# SimpleKeyboard.net
KiCad netlist of a schematic drawn in EAGLE
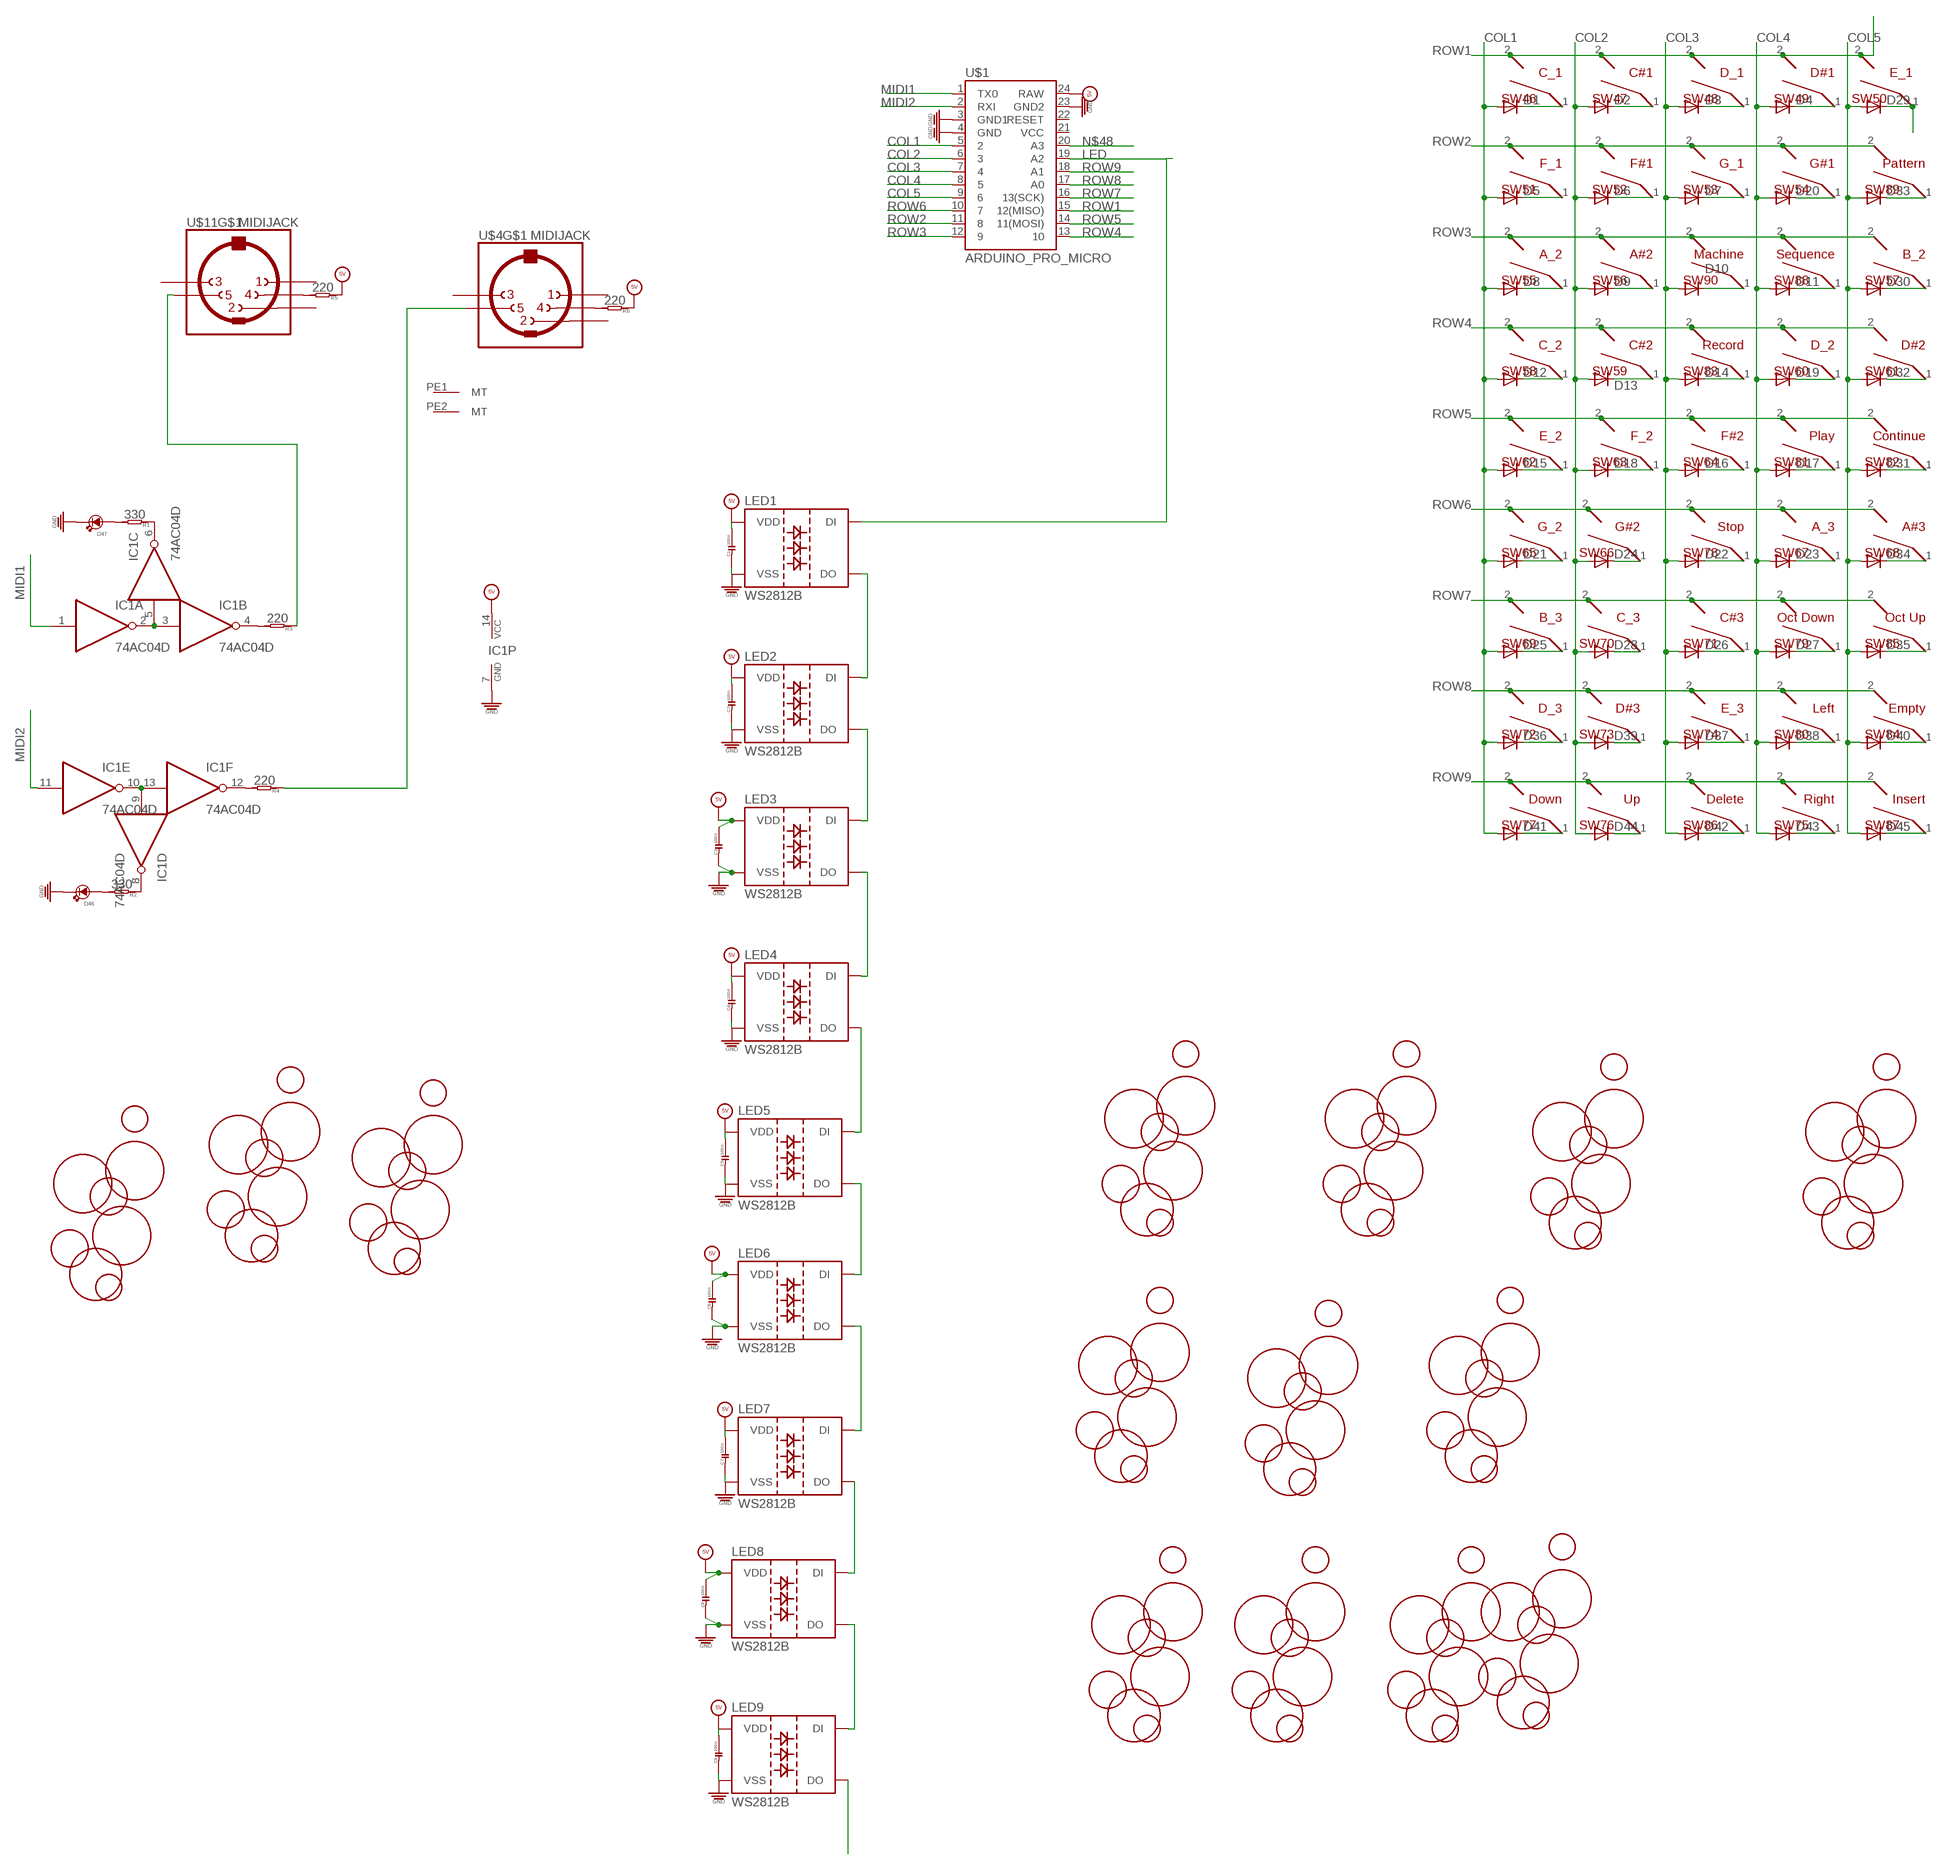
[diagram p0: schematic, sheet 1, part 1 of 2]
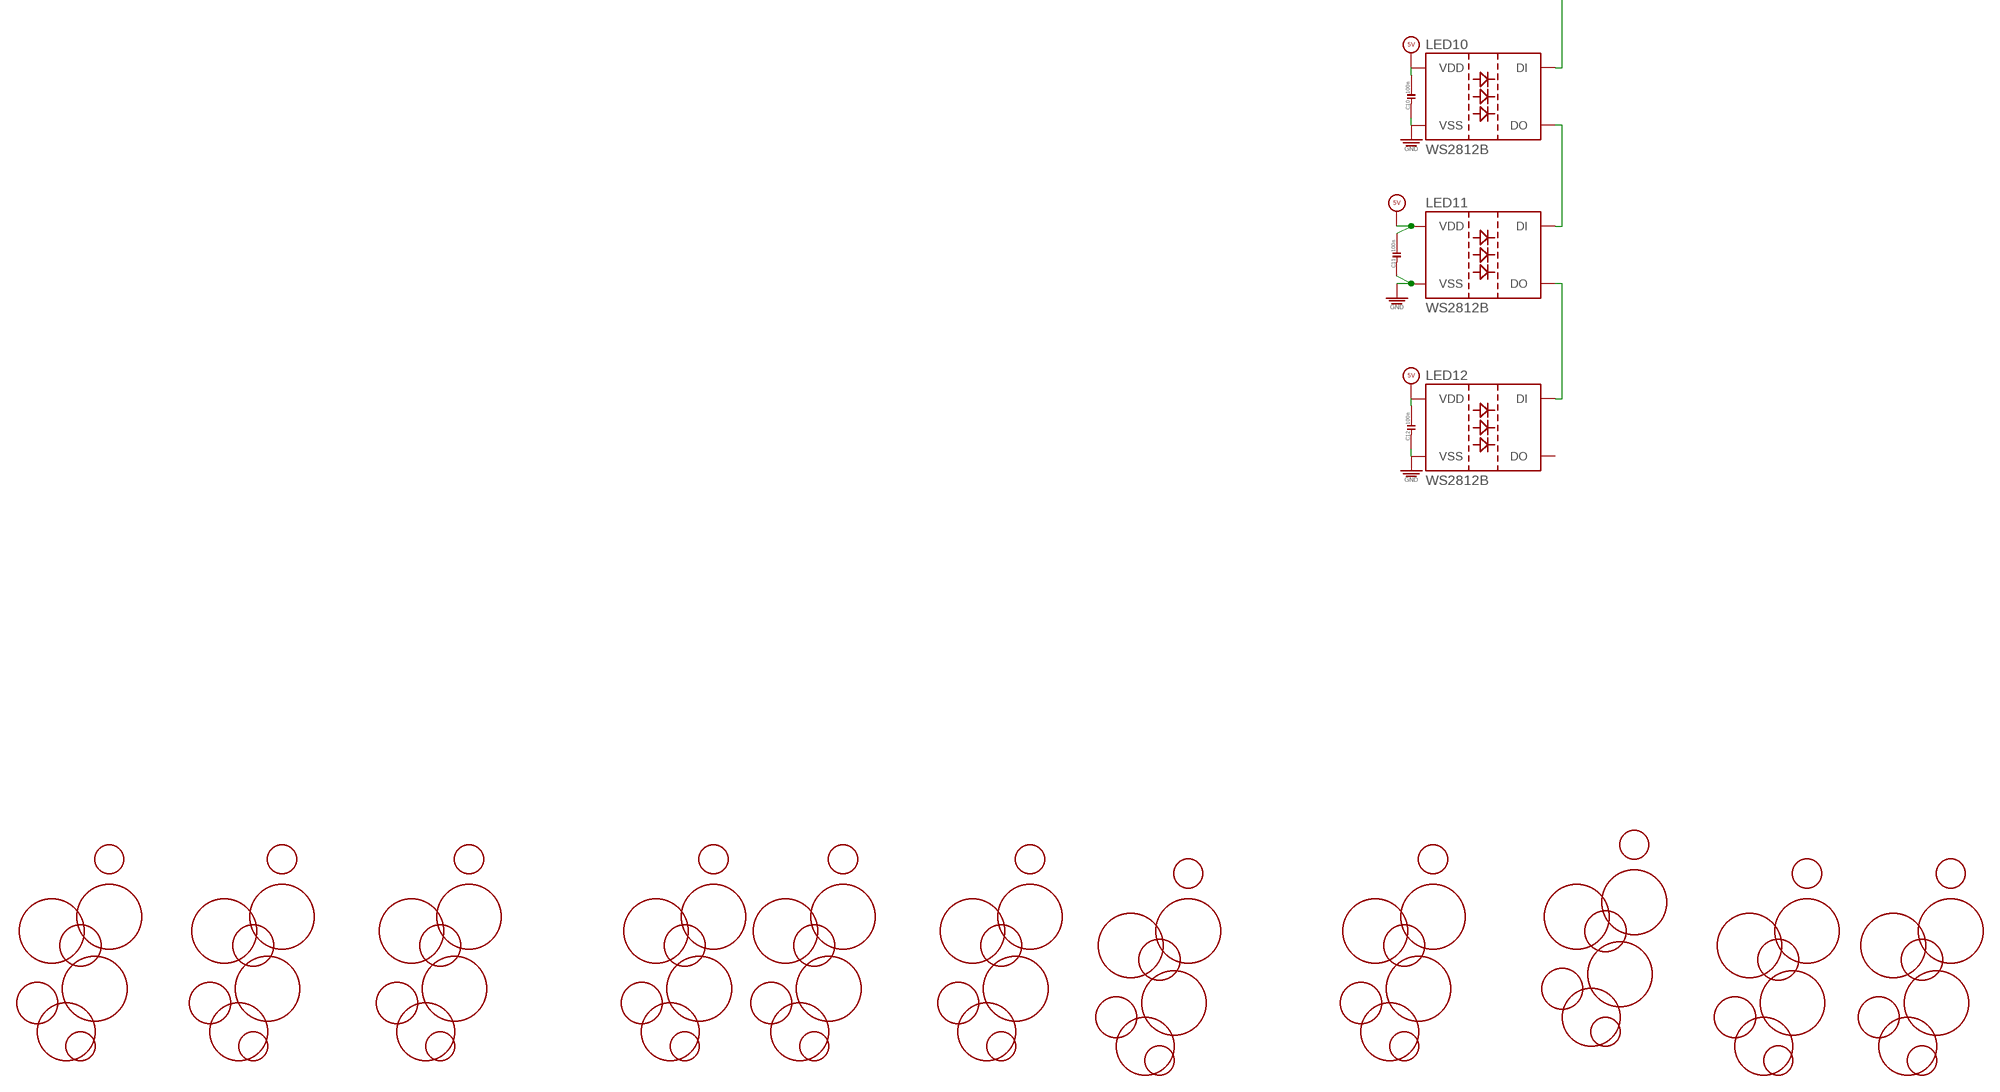
[diagram p1: schematic, sheet 1, part 2 of 2]

(export (version "E")
  (design (tool "Eeschema 10.0.6"))
  (components
    (comp (ref "C1")
      (value "100n")
      (footprint "eagle-import:C0603")
      (libsource (lib "eagle-import") (part "C-0603"))
    )
    (comp (ref "C2")
      (value "100n")
      (footprint "eagle-import:C0603")
      (libsource (lib "eagle-import") (part "C-0603"))
    )
    (comp (ref "C3")
      (value "100n")
      (footprint "eagle-import:C0603")
      (libsource (lib "eagle-import") (part "C-0603"))
    )
    (comp (ref "C4")
      (value "100n")
      (footprint "eagle-import:C0603")
      (libsource (lib "eagle-import") (part "C-0603"))
    )
    (comp (ref "C5")
      (value "100n")
      (footprint "eagle-import:C0603")
      (libsource (lib "eagle-import") (part "C-0603"))
    )
    (comp (ref "C6")
      (value "100n")
      (footprint "eagle-import:C0603")
      (libsource (lib "eagle-import") (part "C-0603"))
    )
    (comp (ref "C7")
      (value "100n")
      (footprint "eagle-import:C0603")
      (libsource (lib "eagle-import") (part "C-0603"))
    )
    (comp (ref "C8")
      (value "100n")
      (footprint "eagle-import:C0603")
      (libsource (lib "eagle-import") (part "C-0603"))
    )
    (comp (ref "C9")
      (value "100n")
      (footprint "eagle-import:C0603")
      (libsource (lib "eagle-import") (part "C-0603"))
    )
    (comp (ref "C10")
      (value "100n")
      (footprint "eagle-import:C0603")
      (libsource (lib "eagle-import") (part "C-0603"))
    )
    (comp (ref "C11")
      (value "100n")
      (footprint "eagle-import:C0603")
      (libsource (lib "eagle-import") (part "C-0603"))
    )
    (comp (ref "C12")
      (value "100n")
      (footprint "eagle-import:C0603")
      (libsource (lib "eagle-import") (part "C-0603"))
    )
    (comp (ref "D1")
      (value "CGRM4001-G")
      (footprint "eagle-import:SOD-123_MINI-SMA")
      (libsource (lib "eagle-import") (part "CGRM400-G1"))
    )
    (comp (ref "D2")
      (value "CGRM4001-G")
      (footprint "eagle-import:SOD-123_MINI-SMA")
      (libsource (lib "eagle-import") (part "CGRM400-G1"))
    )
    (comp (ref "D3")
      (value "CGRM4001-G")
      (footprint "eagle-import:SOD-123_MINI-SMA")
      (libsource (lib "eagle-import") (part "CGRM400-G1"))
    )
    (comp (ref "D4")
      (value "CGRM4001-G")
      (footprint "eagle-import:SOD-123_MINI-SMA")
      (libsource (lib "eagle-import") (part "CGRM400-G1"))
    )
    (comp (ref "D5")
      (value "CGRM4001-G")
      (footprint "eagle-import:SOD-123_MINI-SMA")
      (libsource (lib "eagle-import") (part "CGRM400-G1"))
    )
    (comp (ref "D6")
      (value "CGRM4001-G")
      (footprint "eagle-import:SOD-123_MINI-SMA")
      (libsource (lib "eagle-import") (part "CGRM400-G1"))
    )
    (comp (ref "D7")
      (value "CGRM4001-G")
      (footprint "eagle-import:SOD-123_MINI-SMA")
      (libsource (lib "eagle-import") (part "CGRM400-G1"))
    )
    (comp (ref "D8")
      (value "CGRM4001-G")
      (footprint "eagle-import:SOD-123_MINI-SMA")
      (libsource (lib "eagle-import") (part "CGRM400-G1"))
    )
    (comp (ref "D9")
      (value "CGRM4001-G")
      (footprint "eagle-import:SOD-123_MINI-SMA")
      (libsource (lib "eagle-import") (part "CGRM400-G1"))
    )
    (comp (ref "D10")
      (value "CGRM4001-G")
      (footprint "eagle-import:SOD-123_MINI-SMA")
      (libsource (lib "eagle-import") (part "CGRM400-G1"))
    )
    (comp (ref "D11")
      (value "CGRM4001-G")
      (footprint "eagle-import:SOD-123_MINI-SMA")
      (libsource (lib "eagle-import") (part "CGRM400-G1"))
    )
    (comp (ref "D12")
      (value "CGRM4001-G")
      (footprint "eagle-import:SOD-123_MINI-SMA")
      (libsource (lib "eagle-import") (part "CGRM400-G1"))
    )
    (comp (ref "D13")
      (value "CGRM4001-G")
      (footprint "eagle-import:SOD-123_MINI-SMA")
      (libsource (lib "eagle-import") (part "CGRM400-G1"))
    )
    (comp (ref "D14")
      (value "CGRM4001-G")
      (footprint "eagle-import:SOD-123_MINI-SMA")
      (libsource (lib "eagle-import") (part "CGRM400-G1"))
    )
    (comp (ref "D15")
      (value "CGRM4001-G")
      (footprint "eagle-import:SOD-123_MINI-SMA")
      (libsource (lib "eagle-import") (part "CGRM400-G1"))
    )
    (comp (ref "D16")
      (value "CGRM4001-G")
      (footprint "eagle-import:SOD-123_MINI-SMA")
      (libsource (lib "eagle-import") (part "CGRM400-G1"))
    )
    (comp (ref "D17")
      (value "CGRM4001-G")
      (footprint "eagle-import:SOD-123_MINI-SMA")
      (libsource (lib "eagle-import") (part "CGRM400-G1"))
    )
    (comp (ref "D18")
      (value "CGRM4001-G")
      (footprint "eagle-import:SOD-123_MINI-SMA")
      (libsource (lib "eagle-import") (part "CGRM400-G1"))
    )
    (comp (ref "D19")
      (value "CGRM4001-G")
      (footprint "eagle-import:SOD-123_MINI-SMA")
      (libsource (lib "eagle-import") (part "CGRM400-G1"))
    )
    (comp (ref "D20")
      (value "CGRM4001-G")
      (footprint "eagle-import:SOD-123_MINI-SMA")
      (libsource (lib "eagle-import") (part "CGRM400-G1"))
    )
    (comp (ref "D21")
      (value "CGRM4001-G")
      (footprint "eagle-import:SOD-123_MINI-SMA")
      (libsource (lib "eagle-import") (part "CGRM400-G1"))
    )
    (comp (ref "D22")
      (value "CGRM4001-G")
      (footprint "eagle-import:SOD-123_MINI-SMA")
      (libsource (lib "eagle-import") (part "CGRM400-G1"))
    )
    (comp (ref "D23")
      (value "CGRM4001-G")
      (footprint "eagle-import:SOD-123_MINI-SMA")
      (libsource (lib "eagle-import") (part "CGRM400-G1"))
    )
    (comp (ref "D24")
      (value "CGRM4001-G")
      (footprint "eagle-import:SOD-123_MINI-SMA")
      (libsource (lib "eagle-import") (part "CGRM400-G1"))
    )
    (comp (ref "D25")
      (value "CGRM4001-G")
      (footprint "eagle-import:SOD-123_MINI-SMA")
      (libsource (lib "eagle-import") (part "CGRM400-G1"))
    )
    (comp (ref "D26")
      (value "CGRM4001-G")
      (footprint "eagle-import:SOD-123_MINI-SMA")
      (libsource (lib "eagle-import") (part "CGRM400-G1"))
    )
    (comp (ref "D27")
      (value "CGRM4001-G")
      (footprint "eagle-import:SOD-123_MINI-SMA")
      (libsource (lib "eagle-import") (part "CGRM400-G1"))
    )
    (comp (ref "D28")
      (value "CGRM4001-G")
      (footprint "eagle-import:SOD-123_MINI-SMA")
      (libsource (lib "eagle-import") (part "CGRM400-G1"))
    )
    (comp (ref "D29")
      (value "CGRM4001-G")
      (footprint "eagle-import:SOD-123_MINI-SMA")
      (libsource (lib "eagle-import") (part "CGRM400-G1"))
    )
    (comp (ref "D30")
      (value "CGRM4001-G")
      (footprint "eagle-import:SOD-123_MINI-SMA")
      (libsource (lib "eagle-import") (part "CGRM400-G1"))
    )
    (comp (ref "D31")
      (value "CGRM4001-G")
      (footprint "eagle-import:SOD-123_MINI-SMA")
      (libsource (lib "eagle-import") (part "CGRM400-G1"))
    )
    (comp (ref "D32")
      (value "CGRM4001-G")
      (footprint "eagle-import:SOD-123_MINI-SMA")
      (libsource (lib "eagle-import") (part "CGRM400-G1"))
    )
    (comp (ref "D33")
      (value "CGRM4001-G")
      (footprint "eagle-import:SOD-123_MINI-SMA")
      (libsource (lib "eagle-import") (part "CGRM400-G1"))
    )
    (comp (ref "D34")
      (value "CGRM4001-G")
      (footprint "eagle-import:SOD-123_MINI-SMA")
      (libsource (lib "eagle-import") (part "CGRM400-G1"))
    )
    (comp (ref "D35")
      (value "CGRM4001-G")
      (footprint "eagle-import:SOD-123_MINI-SMA")
      (libsource (lib "eagle-import") (part "CGRM400-G1"))
    )
    (comp (ref "D36")
      (value "CGRM4001-G")
      (footprint "eagle-import:SOD-123_MINI-SMA")
      (libsource (lib "eagle-import") (part "CGRM400-G1"))
    )
    (comp (ref "D37")
      (value "CGRM4001-G")
      (footprint "eagle-import:SOD-123_MINI-SMA")
      (libsource (lib "eagle-import") (part "CGRM400-G1"))
    )
    (comp (ref "D38")
      (value "CGRM4001-G")
      (footprint "eagle-import:SOD-123_MINI-SMA")
      (libsource (lib "eagle-import") (part "CGRM400-G1"))
    )
    (comp (ref "D39")
      (value "CGRM4001-G")
      (footprint "eagle-import:SOD-123_MINI-SMA")
      (libsource (lib "eagle-import") (part "CGRM400-G1"))
    )
    (comp (ref "D40")
      (value "CGRM4001-G")
      (footprint "eagle-import:SOD-123_MINI-SMA")
      (libsource (lib "eagle-import") (part "CGRM400-G1"))
    )
    (comp (ref "D41")
      (value "CGRM4001-G")
      (footprint "eagle-import:SOD-123_MINI-SMA")
      (libsource (lib "eagle-import") (part "CGRM400-G1"))
    )
    (comp (ref "D42")
      (value "CGRM4001-G")
      (footprint "eagle-import:SOD-123_MINI-SMA")
      (libsource (lib "eagle-import") (part "CGRM400-G1"))
    )
    (comp (ref "D43")
      (value "CGRM4001-G")
      (footprint "eagle-import:SOD-123_MINI-SMA")
      (libsource (lib "eagle-import") (part "CGRM400-G1"))
    )
    (comp (ref "D44")
      (value "CGRM4001-G")
      (footprint "eagle-import:SOD-123_MINI-SMA")
      (libsource (lib "eagle-import") (part "CGRM400-G1"))
    )
    (comp (ref "D45")
      (value "CGRM4001-G")
      (footprint "eagle-import:SOD-123_MINI-SMA")
      (libsource (lib "eagle-import") (part "CGRM400-G1"))
    )
    (comp (ref "D46")
      (value "LED3MM")
      (footprint "eagle-import:3MMLED")
      (libsource (lib "eagle-import") (part "LED3MM"))
    )
    (comp (ref "D47")
      (value "LED3MM")
      (footprint "eagle-import:3MMLED")
      (libsource (lib "eagle-import") (part "LED3MM"))
    )
    (comp (ref "IC1")
      (value "74AC04D")
      (footprint "eagle-import:SO14")
      (libsource (lib "eagle-import") (part "7404DAC"))
    )
    (comp (ref "LED1")
      (value "WS2812B")
      (footprint "eagle-import:WS2812B")
      (libsource (lib "eagle-import") (part "WS2812B"))
    )
    (comp (ref "LED2")
      (value "WS2812B")
      (footprint "eagle-import:WS2812B")
      (libsource (lib "eagle-import") (part "WS2812B"))
    )
    (comp (ref "LED3")
      (value "WS2812B")
      (footprint "eagle-import:WS2812B")
      (libsource (lib "eagle-import") (part "WS2812B"))
    )
    (comp (ref "LED4")
      (value "WS2812B")
      (footprint "eagle-import:WS2812B")
      (libsource (lib "eagle-import") (part "WS2812B"))
    )
    (comp (ref "LED5")
      (value "WS2812B")
      (footprint "eagle-import:WS2812B")
      (libsource (lib "eagle-import") (part "WS2812B"))
    )
    (comp (ref "LED6")
      (value "WS2812B")
      (footprint "eagle-import:WS2812B")
      (libsource (lib "eagle-import") (part "WS2812B"))
    )
    (comp (ref "LED7")
      (value "WS2812B")
      (footprint "eagle-import:WS2812B")
      (libsource (lib "eagle-import") (part "WS2812B"))
    )
    (comp (ref "LED8")
      (value "WS2812B")
      (footprint "eagle-import:WS2812B")
      (libsource (lib "eagle-import") (part "WS2812B"))
    )
    (comp (ref "LED9")
      (value "WS2812B")
      (footprint "eagle-import:WS2812B")
      (libsource (lib "eagle-import") (part "WS2812B"))
    )
    (comp (ref "LED10")
      (value "WS2812B")
      (footprint "eagle-import:WS2812B")
      (libsource (lib "eagle-import") (part "WS2812B"))
    )
    (comp (ref "LED11")
      (value "WS2812B")
      (footprint "eagle-import:WS2812B")
      (libsource (lib "eagle-import") (part "WS2812B"))
    )
    (comp (ref "LED12")
      (value "WS2812B")
      (footprint "eagle-import:WS2812B")
      (libsource (lib "eagle-import") (part "WS2812B"))
    )
    (comp (ref "R1")
      (value "330")
      (footprint "eagle-import:R0603")
      (libsource (lib "eagle-import") (part "R-0603"))
    )
    (comp (ref "R2")
      (value "330")
      (footprint "eagle-import:R0603")
      (libsource (lib "eagle-import") (part "R-0603"))
    )
    (comp (ref "R3")
      (value "220")
      (footprint "eagle-import:R0603")
      (libsource (lib "eagle-import") (part "R-0603"))
    )
    (comp (ref "R4")
      (value "220")
      (footprint "eagle-import:R0603")
      (libsource (lib "eagle-import") (part "R-0603"))
    )
    (comp (ref "R5")
      (value "220")
      (footprint "eagle-import:R0603")
      (libsource (lib "eagle-import") (part "R-0603"))
    )
    (comp (ref "R6")
      (value "220")
      (footprint "eagle-import:R0603")
      (libsource (lib "eagle-import") (part "R-0603"))
    )
    (comp (ref "SW46")
      (value "C_1")
      (footprint "eagle-import:MX1A-XXNW")
      (libsource (lib "eagle-import") (part "CHERRY_MX_WITH_FIXING_PINS"))
    )
    (comp (ref "SW47")
      (value "C#1")
      (footprint "eagle-import:MX1A-XXNW")
      (libsource (lib "eagle-import") (part "CHERRY_MX_WITH_FIXING_PINS"))
    )
    (comp (ref "SW48")
      (value "D_1")
      (footprint "eagle-import:MX1A-XXNW")
      (libsource (lib "eagle-import") (part "CHERRY_MX_WITH_FIXING_PINS"))
    )
    (comp (ref "SW49")
      (value "D#1")
      (footprint "eagle-import:MX1A-XXNW")
      (libsource (lib "eagle-import") (part "CHERRY_MX_WITH_FIXING_PINS"))
    )
    (comp (ref "SW50")
      (value "E_1")
      (footprint "eagle-import:MX1A-XXNW")
      (libsource (lib "eagle-import") (part "CHERRY_MX_WITH_FIXING_PINS"))
    )
    (comp (ref "SW51")
      (value "F_1")
      (footprint "eagle-import:MX1A-XXNW")
      (libsource (lib "eagle-import") (part "CHERRY_MX_WITH_FIXING_PINS"))
    )
    (comp (ref "SW52")
      (value "F#1")
      (footprint "eagle-import:MX1A-XXNW")
      (libsource (lib "eagle-import") (part "CHERRY_MX_WITH_FIXING_PINS"))
    )
    (comp (ref "SW53")
      (value "G_1")
      (footprint "eagle-import:MX1A-XXNW")
      (libsource (lib "eagle-import") (part "CHERRY_MX_WITH_FIXING_PINS"))
    )
    (comp (ref "SW54")
      (value "G#1")
      (footprint "eagle-import:MX1A-XXNW")
      (libsource (lib "eagle-import") (part "CHERRY_MX_WITH_FIXING_PINS"))
    )
    (comp (ref "SW55")
      (value "A_2")
      (footprint "eagle-import:MX1A-XXNW")
      (libsource (lib "eagle-import") (part "CHERRY_MX_WITH_FIXING_PINS"))
    )
    (comp (ref "SW56")
      (value "A#2")
      (footprint "eagle-import:MX1A-XXNW")
      (libsource (lib "eagle-import") (part "CHERRY_MX_WITH_FIXING_PINS"))
    )
    (comp (ref "SW57")
      (value "B_2")
      (footprint "eagle-import:MX1A-XXNW")
      (libsource (lib "eagle-import") (part "CHERRY_MX_WITH_FIXING_PINS"))
    )
    (comp (ref "SW58")
      (value "C_2")
      (footprint "eagle-import:MX1A-XXNW")
      (libsource (lib "eagle-import") (part "CHERRY_MX_WITH_FIXING_PINS"))
    )
    (comp (ref "SW59")
      (value "C#2")
      (footprint "eagle-import:MX1A-XXNW")
      (libsource (lib "eagle-import") (part "CHERRY_MX_WITH_FIXING_PINS"))
    )
    (comp (ref "SW60")
      (value "D_2")
      (footprint "eagle-import:MX1A-XXNW")
      (libsource (lib "eagle-import") (part "CHERRY_MX_WITH_FIXING_PINS"))
    )
    (comp (ref "SW61")
      (value "D#2")
      (footprint "eagle-import:MX1A-XXNW")
      (libsource (lib "eagle-import") (part "CHERRY_MX_WITH_FIXING_PINS"))
    )
    (comp (ref "SW62")
      (value "E_2")
      (footprint "eagle-import:MX1A-XXNW")
      (libsource (lib "eagle-import") (part "CHERRY_MX_WITH_FIXING_PINS"))
    )
    (comp (ref "SW63")
      (value "F_2")
      (footprint "eagle-import:MX1A-XXNW")
      (libsource (lib "eagle-import") (part "CHERRY_MX_WITH_FIXING_PINS"))
    )
    (comp (ref "SW64")
      (value "F#2")
      (footprint "eagle-import:MX1A-XXNW")
      (libsource (lib "eagle-import") (part "CHERRY_MX_WITH_FIXING_PINS"))
    )
    (comp (ref "SW65")
      (value "G_2")
      (footprint "eagle-import:MX1A-XXNW")
      (libsource (lib "eagle-import") (part "CHERRY_MX_WITH_FIXING_PINS"))
    )
    (comp (ref "SW66")
      (value "G#2")
      (footprint "eagle-import:MX1A-XXNW")
      (libsource (lib "eagle-import") (part "CHERRY_MX_WITH_FIXING_PINS"))
    )
    (comp (ref "SW67")
      (value "A_3")
      (footprint "eagle-import:MX1A-XXNW")
      (libsource (lib "eagle-import") (part "CHERRY_MX_WITH_FIXING_PINS"))
    )
    (comp (ref "SW68")
      (value "A#3")
      (footprint "eagle-import:MX1A-XXNW")
      (libsource (lib "eagle-import") (part "CHERRY_MX_WITH_FIXING_PINS"))
    )
    (comp (ref "SW69")
      (value "B_3")
      (footprint "eagle-import:MX1A-XXNW")
      (libsource (lib "eagle-import") (part "CHERRY_MX_WITH_FIXING_PINS"))
    )
    (comp (ref "SW70")
      (value "C_3")
      (footprint "eagle-import:MX1A-XXNW")
      (libsource (lib "eagle-import") (part "CHERRY_MX_WITH_FIXING_PINS"))
    )
    (comp (ref "SW71")
      (value "C#3")
      (footprint "eagle-import:MX1A-XXNW")
      (libsource (lib "eagle-import") (part "CHERRY_MX_WITH_FIXING_PINS"))
    )
    (comp (ref "SW72")
      (value "D_3")
      (footprint "eagle-import:MX1A-XXNW")
      (libsource (lib "eagle-import") (part "CHERRY_MX_WITH_FIXING_PINS"))
    )
    (comp (ref "SW73")
      (value "D#3")
      (footprint "eagle-import:MX1A-XXNW")
      (libsource (lib "eagle-import") (part "CHERRY_MX_WITH_FIXING_PINS"))
    )
    (comp (ref "SW74")
      (value "E_3")
      (footprint "eagle-import:MX1A-XXNW")
      (libsource (lib "eagle-import") (part "CHERRY_MX_WITH_FIXING_PINS"))
    )
    (comp (ref "SW75")
      (value "Right")
      (footprint "eagle-import:MX1A-XXNW")
      (libsource (lib "eagle-import") (part "CHERRY_MX_WITH_FIXING_PINS"))
    )
    (comp (ref "SW76")
      (value "Up")
      (footprint "eagle-import:MX1A-XXNW")
      (libsource (lib "eagle-import") (part "CHERRY_MX_WITH_FIXING_PINS"))
    )
    (comp (ref "SW77")
      (value "Down")
      (footprint "eagle-import:MX1A-XXNW")
      (libsource (lib "eagle-import") (part "CHERRY_MX_WITH_FIXING_PINS"))
    )
    (comp (ref "SW78")
      (value "Stop")
      (footprint "eagle-import:MX1A-XXNW")
      (libsource (lib "eagle-import") (part "CHERRY_MX_WITH_FIXING_PINS"))
    )
    (comp (ref "SW79")
      (value "Oct Down")
      (footprint "eagle-import:MX1A-XXNW")
      (libsource (lib "eagle-import") (part "CHERRY_MX_WITH_FIXING_PINS"))
    )
    (comp (ref "SW80")
      (value "Left")
      (footprint "eagle-import:MX1A-XXNW")
      (libsource (lib "eagle-import") (part "CHERRY_MX_WITH_FIXING_PINS"))
    )
    (comp (ref "SW81")
      (value "Play")
      (footprint "eagle-import:MX1A-XXNW")
      (libsource (lib "eagle-import") (part "CHERRY_MX_WITH_FIXING_PINS"))
    )
    (comp (ref "SW82")
      (value "Continue")
      (footprint "eagle-import:MX1A-XXNW")
      (libsource (lib "eagle-import") (part "CHERRY_MX_WITH_FIXING_PINS"))
    )
    (comp (ref "SW83")
      (value "Record")
      (footprint "eagle-import:MX1A-XXNW")
      (libsource (lib "eagle-import") (part "CHERRY_MX_WITH_FIXING_PINS"))
    )
    (comp (ref "SW84")
      (value "Empty")
      (footprint "eagle-import:MX1A-XXNW")
      (libsource (lib "eagle-import") (part "CHERRY_MX_WITH_FIXING_PINS"))
    )
    (comp (ref "SW85")
      (value "Oct Up")
      (footprint "eagle-import:MX1A-XXNW")
      (libsource (lib "eagle-import") (part "CHERRY_MX_WITH_FIXING_PINS"))
    )
    (comp (ref "SW86")
      (value "Delete")
      (footprint "eagle-import:MX1A-XXNW")
      (libsource (lib "eagle-import") (part "CHERRY_MX_WITH_FIXING_PINS"))
    )
    (comp (ref "SW87")
      (value "Insert")
      (footprint "eagle-import:MX1A-XXNW")
      (libsource (lib "eagle-import") (part "CHERRY_MX_WITH_FIXING_PINS"))
    )
    (comp (ref "SW88")
      (value "Sequence")
      (footprint "eagle-import:MX1A-XXNW")
      (libsource (lib "eagle-import") (part "CHERRY_MX_WITH_FIXING_PINS"))
    )
    (comp (ref "SW89")
      (value "Pattern")
      (footprint "eagle-import:MX1A-XXNW")
      (libsource (lib "eagle-import") (part "CHERRY_MX_WITH_FIXING_PINS"))
    )
    (comp (ref "SW90")
      (value "Machine")
      (footprint "eagle-import:MX1A-XXNW")
      (libsource (lib "eagle-import") (part "CHERRY_MX_WITH_FIXING_PINS"))
    )
    (comp (ref "U$1")
      (value "ARDUINO_PRO_MICRO")
      (footprint "eagle-import:ARDUINO_PRO_MICRO")
      (libsource (lib "eagle-import") (part "ARDUINO_PRO_MICRO"))
    )
    (comp (ref "U$4")
      (value "MIDIJACK")
      (footprint "eagle-import:CP-2350")
      (libsource (lib "eagle-import") (part "MIDIJACK"))
    )
    (comp (ref "U$11")
      (value "MIDIJACK")
      (footprint "eagle-import:CP-2350")
      (libsource (lib "eagle-import") (part "MIDIJACK"))
    )
    (comp (ref "U$15")
      (value "BUBBLESDSA_1U")
      (footprint "eagle-import:BUBBLES")
      (libsource (lib "eagle-import") (part "BUBBLESDSA_1U"))
    )
    (comp (ref "U$16")
      (value "BUBBLESDSA_1U")
      (footprint "eagle-import:BUBBLES")
      (libsource (lib "eagle-import") (part "BUBBLESDSA_1U"))
    )
    (comp (ref "U$17")
      (value "BUBBLESDSA_1U")
      (footprint "eagle-import:BUBBLES")
      (libsource (lib "eagle-import") (part "BUBBLESDSA_1U"))
    )
    (comp (ref "U$18")
      (value "BUBBLESDSA_1U")
      (footprint "eagle-import:BUBBLES")
      (libsource (lib "eagle-import") (part "BUBBLESDSA_1U"))
    )
    (comp (ref "U$19")
      (value "BUBBLESDSA_1U")
      (footprint "eagle-import:BUBBLES")
      (libsource (lib "eagle-import") (part "BUBBLESDSA_1U"))
    )
    (comp (ref "U$20")
      (value "BUBBLESDSA_1U")
      (footprint "eagle-import:BUBBLES")
      (libsource (lib "eagle-import") (part "BUBBLESDSA_1U"))
    )
    (comp (ref "U$21")
      (value "BUBBLESDSA_1U_HALF")
      (footprint "eagle-import:BUBBLES_HALF")
      (libsource (lib "eagle-import") (part "BUBBLESDSA_1U_HALF"))
    )
    (comp (ref "U$22")
      (value "BUBBLESDSA_1U_HALF")
      (footprint "eagle-import:BUBBLES_HALF")
      (libsource (lib "eagle-import") (part "BUBBLESDSA_1U_HALF"))
    )
    (comp (ref "U$28")
      (value "BUBBLESINV")
      (footprint "eagle-import:BUBBLES_INV")
      (libsource (lib "eagle-import") (part "BUBBLESINV"))
    )
    (comp (ref "U$29")
      (value "BUBBLESINV")
      (footprint "eagle-import:BUBBLES_INV")
      (libsource (lib "eagle-import") (part "BUBBLESINV"))
    )
    (comp (ref "U$30")
      (value "BUBBLESINV")
      (footprint "eagle-import:BUBBLES_INV")
      (libsource (lib "eagle-import") (part "BUBBLESINV"))
    )
    (comp (ref "U$31")
      (value "BUBBLESINV")
      (footprint "eagle-import:BUBBLES_INV")
      (libsource (lib "eagle-import") (part "BUBBLESINV"))
    )
    (comp (ref "U$32")
      (value "BUBBLESINV")
      (footprint "eagle-import:BUBBLES_INV")
      (libsource (lib "eagle-import") (part "BUBBLESINV"))
    )
    (comp (ref "U$33")
      (value "BUBBLESDSA_1U_HALF")
      (footprint "eagle-import:BUBBLES_HALF")
      (libsource (lib "eagle-import") (part "BUBBLESDSA_1U_HALF"))
    )
    (comp (ref "U$34")
      (value "BUBBLESONE")
      (footprint "eagle-import:BUBBLES_ONE")
      (libsource (lib "eagle-import") (part "BUBBLESONE"))
    )
    (comp (ref "U$35")
      (value "BUBBLESONE")
      (footprint "eagle-import:BUBBLES_ONE")
      (libsource (lib "eagle-import") (part "BUBBLESONE"))
    )
    (comp (ref "U$36")
      (value "BUBBLESONE")
      (footprint "eagle-import:BUBBLES_ONE")
      (libsource (lib "eagle-import") (part "BUBBLESONE"))
    )
    (comp (ref "U$37")
      (value "BUBBLESONE")
      (footprint "eagle-import:BUBBLES_ONE")
      (libsource (lib "eagle-import") (part "BUBBLESONE"))
    )
    (comp (ref "U$38")
      (value "BUBBLESONE")
      (footprint "eagle-import:BUBBLES_ONE")
      (libsource (lib "eagle-import") (part "BUBBLESONE"))
    )
    (comp (ref "U$39")
      (value "BUBBLESONE")
      (footprint "eagle-import:BUBBLES_ONE")
      (libsource (lib "eagle-import") (part "BUBBLESONE"))
    )
    (comp (ref "U$40")
      (value "BUBBLESONE")
      (footprint "eagle-import:BUBBLES_ONE")
      (libsource (lib "eagle-import") (part "BUBBLESONE"))
    )
    (comp (ref "U$41")
      (value "BUBBLESONE")
      (footprint "eagle-import:BUBBLES_ONE")
      (libsource (lib "eagle-import") (part "BUBBLESONE"))
    )
    (comp (ref "U$42")
      (value "BUBBLESONE")
      (footprint "eagle-import:BUBBLES_ONE")
      (libsource (lib "eagle-import") (part "BUBBLESONE"))
    )
    (comp (ref "U$43")
      (value "BUBBLESONE")
      (footprint "eagle-import:BUBBLES_ONE")
      (libsource (lib "eagle-import") (part "BUBBLESONE"))
    )
    (comp (ref "U$44")
      (value "BUBBLESONE")
      (footprint "eagle-import:BUBBLES_ONE")
      (libsource (lib "eagle-import") (part "BUBBLESONE"))
    )
  )
  (nets
    (net (code "1") (name "/COL1") (class "Default")
      (node (ref "D1") (pin "A") (pinfunction "A_A") (pintype "passive"))
      (node (ref "D12") (pin "A") (pinfunction "A_A") (pintype "passive"))
      (node (ref "D15") (pin "A") (pinfunction "A_A") (pintype "passive"))
      (node (ref "D21") (pin "A") (pinfunction "A_A") (pintype "passive"))
      (node (ref "D25") (pin "A") (pinfunction "A_A") (pintype "passive"))
      (node (ref "D36") (pin "A") (pinfunction "A_A") (pintype "passive"))
      (node (ref "D41") (pin "A") (pinfunction "A_A") (pintype "passive"))
      (node (ref "D5") (pin "A") (pinfunction "A_A") (pintype "passive"))
      (node (ref "D8") (pin "A") (pinfunction "A_A") (pintype "passive"))
      (node (ref "U$1") (pin "5") (pinfunction "2_5") (pintype "bidirectional"))
    )
    (net (code "2") (name "/COL2") (class "Default")
      (node (ref "D13") (pin "A") (pinfunction "A_A") (pintype "passive"))
      (node (ref "D18") (pin "A") (pinfunction "A_A") (pintype "passive"))
      (node (ref "D2") (pin "A") (pinfunction "A_A") (pintype "passive"))
      (node (ref "D24") (pin "A") (pinfunction "A_A") (pintype "passive"))
      (node (ref "D28") (pin "A") (pinfunction "A_A") (pintype "passive"))
      (node (ref "D39") (pin "A") (pinfunction "A_A") (pintype "passive"))
      (node (ref "D44") (pin "A") (pinfunction "A_A") (pintype "passive"))
      (node (ref "D6") (pin "A") (pinfunction "A_A") (pintype "passive"))
      (node (ref "D9") (pin "A") (pinfunction "A_A") (pintype "passive"))
      (node (ref "U$1") (pin "6") (pinfunction "3_6") (pintype "bidirectional"))
    )
    (net (code "3") (name "/COL3") (class "Default")
      (node (ref "D10") (pin "A") (pinfunction "A_A") (pintype "passive"))
      (node (ref "D14") (pin "A") (pinfunction "A_A") (pintype "passive"))
      (node (ref "D16") (pin "A") (pinfunction "A_A") (pintype "passive"))
      (node (ref "D22") (pin "A") (pinfunction "A_A") (pintype "passive"))
      (node (ref "D26") (pin "A") (pinfunction "A_A") (pintype "passive"))
      (node (ref "D3") (pin "A") (pinfunction "A_A") (pintype "passive"))
      (node (ref "D37") (pin "A") (pinfunction "A_A") (pintype "passive"))
      (node (ref "D42") (pin "A") (pinfunction "A_A") (pintype "passive"))
      (node (ref "D7") (pin "A") (pinfunction "A_A") (pintype "passive"))
      (node (ref "U$1") (pin "7") (pinfunction "4_7") (pintype "bidirectional"))
    )
    (net (code "4") (name "/COL4") (class "Default")
      (node (ref "D11") (pin "A") (pinfunction "A_A") (pintype "passive"))
      (node (ref "D17") (pin "A") (pinfunction "A_A") (pintype "passive"))
      (node (ref "D19") (pin "A") (pinfunction "A_A") (pintype "passive"))
      (node (ref "D20") (pin "A") (pinfunction "A_A") (pintype "passive"))
      (node (ref "D23") (pin "A") (pinfunction "A_A") (pintype "passive"))
      (node (ref "D27") (pin "A") (pinfunction "A_A") (pintype "passive"))
      (node (ref "D38") (pin "A") (pinfunction "A_A") (pintype "passive"))
      (node (ref "D4") (pin "A") (pinfunction "A_A") (pintype "passive"))
      (node (ref "D43") (pin "A") (pinfunction "A_A") (pintype "passive"))
      (node (ref "U$1") (pin "8") (pinfunction "5_8") (pintype "bidirectional"))
    )
    (net (code "5") (name "/COL5") (class "Default")
      (node (ref "D29") (pin "A") (pinfunction "A_A") (pintype "passive"))
      (node (ref "D30") (pin "A") (pinfunction "A_A") (pintype "passive"))
      (node (ref "D31") (pin "A") (pinfunction "A_A") (pintype "passive"))
      (node (ref "D32") (pin "A") (pinfunction "A_A") (pintype "passive"))
      (node (ref "D33") (pin "A") (pinfunction "A_A") (pintype "passive"))
      (node (ref "D34") (pin "A") (pinfunction "A_A") (pintype "passive"))
      (node (ref "D35") (pin "A") (pinfunction "A_A") (pintype "passive"))
      (node (ref "D40") (pin "A") (pinfunction "A_A") (pintype "passive"))
      (node (ref "D45") (pin "A") (pinfunction "A_A") (pintype "passive"))
      (node (ref "U$1") (pin "9") (pinfunction "6_9") (pintype "bidirectional"))
    )
    (net (code "6") (name "/LED") (class "Default")
      (node (ref "LED1") (pin "DIN") (pinfunction "DI_DIN") (pintype "bidirectional"))
      (node (ref "U$1") (pin "19") (pinfunction "A2_19") (pintype "bidirectional"))
    )
    (net (code "7") (name "/MIDI1") (class "Default")
      (node (ref "IC1") (pin "1") (pinfunction "I_1") (pintype "input"))
      (node (ref "U$1") (pin "1") (pinfunction "TX0_1") (pintype "bidirectional"))
    )
    (net (code "8") (name "/MIDI2") (class "Default")
      (node (ref "IC1") (pin "11") (pinfunction "I_11") (pintype "input"))
      (node (ref "U$1") (pin "2") (pinfunction "RXI_2") (pintype "bidirectional"))
    )
    (net (code "9") (name "/N$48") (class "Default")
      (node (ref "U$1") (pin "20") (pinfunction "A3_20") (pintype "bidirectional"))
    )
    (net (code "10") (name "/ROW1") (class "Default")
      (node (ref "SW46") (pin "2") (pinfunction "2_2") (pintype "passive"))
      (node (ref "SW47") (pin "2") (pinfunction "2_2") (pintype "passive"))
      (node (ref "SW48") (pin "2") (pinfunction "2_2") (pintype "passive"))
      (node (ref "SW49") (pin "2") (pinfunction "2_2") (pintype "passive"))
      (node (ref "SW50") (pin "2") (pinfunction "2_2") (pintype "passive"))
      (node (ref "U$1") (pin "15") (pinfunction "12(MISO)_15") (pintype "bidirectional"))
    )
    (net (code "11") (name "/ROW2") (class "Default")
      (node (ref "SW51") (pin "2") (pinfunction "2_2") (pintype "passive"))
      (node (ref "SW52") (pin "2") (pinfunction "2_2") (pintype "passive"))
      (node (ref "SW53") (pin "2") (pinfunction "2_2") (pintype "passive"))
      (node (ref "SW54") (pin "2") (pinfunction "2_2") (pintype "passive"))
      (node (ref "SW89") (pin "2") (pinfunction "2_2") (pintype "passive"))
      (node (ref "U$1") (pin "11") (pinfunction "8_11") (pintype "bidirectional"))
    )
    (net (code "12") (name "/ROW3") (class "Default")
      (node (ref "SW55") (pin "2") (pinfunction "2_2") (pintype "passive"))
      (node (ref "SW56") (pin "2") (pinfunction "2_2") (pintype "passive"))
      (node (ref "SW57") (pin "2") (pinfunction "2_2") (pintype "passive"))
      (node (ref "SW88") (pin "2") (pinfunction "2_2") (pintype "passive"))
      (node (ref "SW90") (pin "2") (pinfunction "2_2") (pintype "passive"))
      (node (ref "U$1") (pin "12") (pinfunction "9_12") (pintype "bidirectional"))
    )
    (net (code "13") (name "/ROW4") (class "Default")
      (node (ref "SW58") (pin "2") (pinfunction "2_2") (pintype "passive"))
      (node (ref "SW59") (pin "2") (pinfunction "2_2") (pintype "passive"))
      (node (ref "SW60") (pin "2") (pinfunction "2_2") (pintype "passive"))
      (node (ref "SW61") (pin "2") (pinfunction "2_2") (pintype "passive"))
      (node (ref "SW83") (pin "2") (pinfunction "2_2") (pintype "passive"))
      (node (ref "U$1") (pin "13") (pinfunction "10_13") (pintype "bidirectional"))
    )
    (net (code "14") (name "/ROW5") (class "Default")
      (node (ref "SW62") (pin "2") (pinfunction "2_2") (pintype "passive"))
      (node (ref "SW63") (pin "2") (pinfunction "2_2") (pintype "passive"))
      (node (ref "SW64") (pin "2") (pinfunction "2_2") (pintype "passive"))
      (node (ref "SW81") (pin "2") (pinfunction "2_2") (pintype "passive"))
      (node (ref "SW82") (pin "2") (pinfunction "2_2") (pintype "passive"))
      (node (ref "U$1") (pin "14") (pinfunction "11(MOSI)_14") (pintype "bidirectional"))
    )
    (net (code "15") (name "/ROW6") (class "Default")
      (node (ref "SW65") (pin "2") (pinfunction "2_2") (pintype "passive"))
      (node (ref "SW66") (pin "2") (pinfunction "2_2") (pintype "passive"))
      (node (ref "SW67") (pin "2") (pinfunction "2_2") (pintype "passive"))
      (node (ref "SW68") (pin "2") (pinfunction "2_2") (pintype "passive"))
      (node (ref "SW78") (pin "2") (pinfunction "2_2") (pintype "passive"))
      (node (ref "U$1") (pin "10") (pinfunction "7_10") (pintype "bidirectional"))
    )
    (net (code "16") (name "/ROW7") (class "Default")
      (node (ref "SW69") (pin "2") (pinfunction "2_2") (pintype "passive"))
      (node (ref "SW70") (pin "2") (pinfunction "2_2") (pintype "passive"))
      (node (ref "SW71") (pin "2") (pinfunction "2_2") (pintype "passive"))
      (node (ref "SW79") (pin "2") (pinfunction "2_2") (pintype "passive"))
      (node (ref "SW85") (pin "2") (pinfunction "2_2") (pintype "passive"))
      (node (ref "U$1") (pin "16") (pinfunction "13(SCK)_16") (pintype "bidirectional"))
    )
    (net (code "17") (name "/ROW8") (class "Default")
      (node (ref "SW72") (pin "2") (pinfunction "2_2") (pintype "passive"))
      (node (ref "SW73") (pin "2") (pinfunction "2_2") (pintype "passive"))
      (node (ref "SW74") (pin "2") (pinfunction "2_2") (pintype "passive"))
      (node (ref "SW80") (pin "2") (pinfunction "2_2") (pintype "passive"))
      (node (ref "SW84") (pin "2") (pinfunction "2_2") (pintype "passive"))
      (node (ref "U$1") (pin "17") (pinfunction "A0_17") (pintype "bidirectional"))
    )
    (net (code "18") (name "/ROW9") (class "Default")
      (node (ref "SW75") (pin "2") (pinfunction "2_2") (pintype "passive"))
      (node (ref "SW76") (pin "2") (pinfunction "2_2") (pintype "passive"))
      (node (ref "SW77") (pin "2") (pinfunction "2_2") (pintype "passive"))
      (node (ref "SW86") (pin "2") (pinfunction "2_2") (pintype "passive"))
      (node (ref "SW87") (pin "2") (pinfunction "2_2") (pintype "passive"))
      (node (ref "U$1") (pin "18") (pinfunction "A1_18") (pintype "bidirectional"))
    )
    (net (code "19") (name "5V") (class "Default")
      (node (ref "C1") (pin "2") (pinfunction "2_2") (pintype "bidirectional"))
      (node (ref "C10") (pin "2") (pinfunction "2_2") (pintype "bidirectional"))
      (node (ref "C11") (pin "2") (pinfunction "2_2") (pintype "bidirectional"))
      (node (ref "C12") (pin "2") (pinfunction "2_2") (pintype "bidirectional"))
      (node (ref "C2") (pin "2") (pinfunction "2_2") (pintype "bidirectional"))
      (node (ref "C3") (pin "2") (pinfunction "2_2") (pintype "bidirectional"))
      (node (ref "C4") (pin "2") (pinfunction "2_2") (pintype "bidirectional"))
      (node (ref "C5") (pin "2") (pinfunction "2_2") (pintype "bidirectional"))
      (node (ref "C6") (pin "2") (pinfunction "2_2") (pintype "bidirectional"))
      (node (ref "C7") (pin "2") (pinfunction "2_2") (pintype "bidirectional"))
      (node (ref "C8") (pin "2") (pinfunction "2_2") (pintype "bidirectional"))
      (node (ref "C9") (pin "2") (pinfunction "2_2") (pintype "bidirectional"))
      (node (ref "IC1") (pin "14") (pinfunction "VCC_14") (pintype "power_in"))
      (node (ref "LED1") (pin "VDD") (pinfunction "VDD_VDD") (pintype "bidirectional"))
      (node (ref "LED10") (pin "VDD") (pinfunction "VDD_VDD") (pintype "bidirectional"))
      (node (ref "LED11") (pin "VDD") (pinfunction "VDD_VDD") (pintype "bidirectional"))
      (node (ref "LED12") (pin "VDD") (pinfunction "VDD_VDD") (pintype "bidirectional"))
      (node (ref "LED2") (pin "VDD") (pinfunction "VDD_VDD") (pintype "bidirectional"))
      (node (ref "LED3") (pin "VDD") (pinfunction "VDD_VDD") (pintype "bidirectional"))
      (node (ref "LED4") (pin "VDD") (pinfunction "VDD_VDD") (pintype "bidirectional"))
      (node (ref "LED5") (pin "VDD") (pinfunction "VDD_VDD") (pintype "bidirectional"))
      (node (ref "LED6") (pin "VDD") (pinfunction "VDD_VDD") (pintype "bidirectional"))
      (node (ref "LED7") (pin "VDD") (pinfunction "VDD_VDD") (pintype "bidirectional"))
      (node (ref "LED8") (pin "VDD") (pinfunction "VDD_VDD") (pintype "bidirectional"))
      (node (ref "LED9") (pin "VDD") (pinfunction "VDD_VDD") (pintype "bidirectional"))
      (node (ref "R5") (pin "1") (pinfunction "1_1") (pintype "bidirectional"))
      (node (ref "R6") (pin "1") (pinfunction "1_1") (pintype "bidirectional"))
      (node (ref "U$1") (pin "24") (pinfunction "RAW_24") (pintype "bidirectional"))
    )
    (net (code "20") (name "GND") (class "Default")
      (node (ref "C1") (pin "1") (pinfunction "1_1") (pintype "bidirectional"))
      (node (ref "C10") (pin "1") (pinfunction "1_1") (pintype "bidirectional"))
      (node (ref "C11") (pin "1") (pinfunction "1_1") (pintype "bidirectional"))
      (node (ref "C12") (pin "1") (pinfunction "1_1") (pintype "bidirectional"))
      (node (ref "C2") (pin "1") (pinfunction "1_1") (pintype "bidirectional"))
      (node (ref "C3") (pin "1") (pinfunction "1_1") (pintype "bidirectional"))
      (node (ref "C4") (pin "1") (pinfunction "1_1") (pintype "bidirectional"))
      (node (ref "C5") (pin "1") (pinfunction "1_1") (pintype "bidirectional"))
      (node (ref "C6") (pin "1") (pinfunction "1_1") (pintype "bidirectional"))
      (node (ref "C7") (pin "1") (pinfunction "1_1") (pintype "bidirectional"))
      (node (ref "C8") (pin "1") (pinfunction "1_1") (pintype "bidirectional"))
      (node (ref "C9") (pin "1") (pinfunction "1_1") (pintype "bidirectional"))
      (node (ref "D46") (pin "-") (pinfunction "-_-") (pintype "passive"))
      (node (ref "D47") (pin "-") (pinfunction "-_-") (pintype "passive"))
      (node (ref "IC1") (pin "7") (pinfunction "GND_7") (pintype "power_in"))
      (node (ref "LED1") (pin "VSS") (pinfunction "VSS_VSS") (pintype "bidirectional"))
      (node (ref "LED10") (pin "VSS") (pinfunction "VSS_VSS") (pintype "bidirectional"))
      (node (ref "LED11") (pin "VSS") (pinfunction "VSS_VSS") (pintype "bidirectional"))
      (node (ref "LED12") (pin "VSS") (pinfunction "VSS_VSS") (pintype "bidirectional"))
      (node (ref "LED2") (pin "VSS") (pinfunction "VSS_VSS") (pintype "bidirectional"))
      (node (ref "LED3") (pin "VSS") (pinfunction "VSS_VSS") (pintype "bidirectional"))
      (node (ref "LED4") (pin "VSS") (pinfunction "VSS_VSS") (pintype "bidirectional"))
      (node (ref "LED5") (pin "VSS") (pinfunction "VSS_VSS") (pintype "bidirectional"))
      (node (ref "LED6") (pin "VSS") (pinfunction "VSS_VSS") (pintype "bidirectional"))
      (node (ref "LED7") (pin "VSS") (pinfunction "VSS_VSS") (pintype "bidirectional"))
      (node (ref "LED8") (pin "VSS") (pinfunction "VSS_VSS") (pintype "bidirectional"))
      (node (ref "LED9") (pin "VSS") (pinfunction "VSS_VSS") (pintype "bidirectional"))
      (node (ref "U$1") (pin "23") (pinfunction "GND2_23") (pintype "bidirectional"))
      (node (ref "U$1") (pin "3") (pinfunction "GND1_3") (pintype "bidirectional"))
      (node (ref "U$1") (pin "4") (pinfunction "GND_4") (pintype "bidirectional"))
    )
    (net (code "21") (name "Net-(D1-PadC)") (class "Default")
      (node (ref "D1") (pin "C") (pinfunction "C_C") (pintype "passive"))
      (node (ref "SW46") (pin "1") (pinfunction "1_1") (pintype "passive"))
    )
    (net (code "22") (name "Net-(D2-PadC)") (class "Default")
      (node (ref "D2") (pin "C") (pinfunction "C_C") (pintype "passive"))
      (node (ref "SW47") (pin "1") (pinfunction "1_1") (pintype "passive"))
    )
    (net (code "23") (name "Net-(D3-PadC)") (class "Default")
      (node (ref "D3") (pin "C") (pinfunction "C_C") (pintype "passive"))
      (node (ref "SW48") (pin "1") (pinfunction "1_1") (pintype "passive"))
    )
    (net (code "24") (name "Net-(D4-PadC)") (class "Default")
      (node (ref "D4") (pin "C") (pinfunction "C_C") (pintype "passive"))
      (node (ref "SW49") (pin "1") (pinfunction "1_1") (pintype "passive"))
    )
    (net (code "25") (name "Net-(D5-PadC)") (class "Default")
      (node (ref "D5") (pin "C") (pinfunction "C_C") (pintype "passive"))
      (node (ref "SW51") (pin "1") (pinfunction "1_1") (pintype "passive"))
    )
    (net (code "26") (name "Net-(D6-PadC)") (class "Default")
      (node (ref "D6") (pin "C") (pinfunction "C_C") (pintype "passive"))
      (node (ref "SW52") (pin "1") (pinfunction "1_1") (pintype "passive"))
    )
    (net (code "27") (name "Net-(D7-PadC)") (class "Default")
      (node (ref "D7") (pin "C") (pinfunction "C_C") (pintype "passive"))
      (node (ref "SW53") (pin "1") (pinfunction "1_1") (pintype "passive"))
    )
    (net (code "28") (name "Net-(D8-PadC)") (class "Default")
      (node (ref "D8") (pin "C") (pinfunction "C_C") (pintype "passive"))
      (node (ref "SW55") (pin "1") (pinfunction "1_1") (pintype "passive"))
    )
    (net (code "29") (name "Net-(D9-PadC)") (class "Default")
      (node (ref "D9") (pin "C") (pinfunction "C_C") (pintype "passive"))
      (node (ref "SW56") (pin "1") (pinfunction "1_1") (pintype "passive"))
    )
    (net (code "30") (name "Net-(D10-PadC)") (class "Default")
      (node (ref "D10") (pin "C") (pinfunction "C_C") (pintype "passive"))
      (node (ref "SW90") (pin "1") (pinfunction "1_1") (pintype "passive"))
    )
    (net (code "31") (name "Net-(D11-PadC)") (class "Default")
      (node (ref "D11") (pin "C") (pinfunction "C_C") (pintype "passive"))
      (node (ref "SW88") (pin "1") (pinfunction "1_1") (pintype "passive"))
    )
    (net (code "32") (name "Net-(D12-PadC)") (class "Default")
      (node (ref "D12") (pin "C") (pinfunction "C_C") (pintype "passive"))
      (node (ref "SW58") (pin "1") (pinfunction "1_1") (pintype "passive"))
    )
    (net (code "33") (name "Net-(D13-PadC)") (class "Default")
      (node (ref "D13") (pin "C") (pinfunction "C_C") (pintype "passive"))
      (node (ref "SW59") (pin "1") (pinfunction "1_1") (pintype "passive"))
    )
    (net (code "34") (name "Net-(D14-PadC)") (class "Default")
      (node (ref "D14") (pin "C") (pinfunction "C_C") (pintype "passive"))
      (node (ref "SW83") (pin "1") (pinfunction "1_1") (pintype "passive"))
    )
    (net (code "35") (name "Net-(D15-PadC)") (class "Default")
      (node (ref "D15") (pin "C") (pinfunction "C_C") (pintype "passive"))
      (node (ref "SW62") (pin "1") (pinfunction "1_1") (pintype "passive"))
    )
    (net (code "36") (name "Net-(D16-PadC)") (class "Default")
      (node (ref "D16") (pin "C") (pinfunction "C_C") (pintype "passive"))
      (node (ref "SW64") (pin "1") (pinfunction "1_1") (pintype "passive"))
    )
    (net (code "37") (name "Net-(D17-PadC)") (class "Default")
      (node (ref "D17") (pin "C") (pinfunction "C_C") (pintype "passive"))
      (node (ref "SW81") (pin "1") (pinfunction "1_1") (pintype "passive"))
    )
    (net (code "38") (name "Net-(D18-PadC)") (class "Default")
      (node (ref "D18") (pin "C") (pinfunction "C_C") (pintype "passive"))
      (node (ref "SW63") (pin "1") (pinfunction "1_1") (pintype "passive"))
    )
    (net (code "39") (name "Net-(D19-PadC)") (class "Default")
      (node (ref "D19") (pin "C") (pinfunction "C_C") (pintype "passive"))
      (node (ref "SW60") (pin "1") (pinfunction "1_1") (pintype "passive"))
    )
    (net (code "40") (name "Net-(D20-PadC)") (class "Default")
      (node (ref "D20") (pin "C") (pinfunction "C_C") (pintype "passive"))
      (node (ref "SW54") (pin "1") (pinfunction "1_1") (pintype "passive"))
    )
    (net (code "41") (name "Net-(D21-PadC)") (class "Default")
      (node (ref "D21") (pin "C") (pinfunction "C_C") (pintype "passive"))
      (node (ref "SW65") (pin "1") (pinfunction "1_1") (pintype "passive"))
    )
    (net (code "42") (name "Net-(D22-PadC)") (class "Default")
      (node (ref "D22") (pin "C") (pinfunction "C_C") (pintype "passive"))
      (node (ref "SW78") (pin "1") (pinfunction "1_1") (pintype "passive"))
    )
    (net (code "43") (name "Net-(D23-PadC)") (class "Default")
      (node (ref "D23") (pin "C") (pinfunction "C_C") (pintype "passive"))
      (node (ref "SW67") (pin "1") (pinfunction "1_1") (pintype "passive"))
    )
    (net (code "44") (name "Net-(D24-PadC)") (class "Default")
      (node (ref "D24") (pin "C") (pinfunction "C_C") (pintype "passive"))
      (node (ref "SW66") (pin "1") (pinfunction "1_1") (pintype "passive"))
    )
    (net (code "45") (name "Net-(D25-PadC)") (class "Default")
      (node (ref "D25") (pin "C") (pinfunction "C_C") (pintype "passive"))
      (node (ref "SW69") (pin "1") (pinfunction "1_1") (pintype "passive"))
    )
    (net (code "46") (name "Net-(D26-PadC)") (class "Default")
      (node (ref "D26") (pin "C") (pinfunction "C_C") (pintype "passive"))
      (node (ref "SW71") (pin "1") (pinfunction "1_1") (pintype "passive"))
    )
    (net (code "47") (name "Net-(D27-PadC)") (class "Default")
      (node (ref "D27") (pin "C") (pinfunction "C_C") (pintype "passive"))
      (node (ref "SW79") (pin "1") (pinfunction "1_1") (pintype "passive"))
    )
    (net (code "48") (name "Net-(D28-PadC)") (class "Default")
      (node (ref "D28") (pin "C") (pinfunction "C_C") (pintype "passive"))
      (node (ref "SW70") (pin "1") (pinfunction "1_1") (pintype "passive"))
    )
    (net (code "49") (name "Net-(D29-PadC)") (class "Default")
      (node (ref "D29") (pin "C") (pinfunction "C_C") (pintype "passive"))
      (node (ref "SW50") (pin "1") (pinfunction "1_1") (pintype "passive"))
    )
    (net (code "50") (name "Net-(D30-PadC)") (class "Default")
      (node (ref "D30") (pin "C") (pinfunction "C_C") (pintype "passive"))
      (node (ref "SW57") (pin "1") (pinfunction "1_1") (pintype "passive"))
    )
    (net (code "51") (name "Net-(D31-PadC)") (class "Default")
      (node (ref "D31") (pin "C") (pinfunction "C_C") (pintype "passive"))
      (node (ref "SW82") (pin "1") (pinfunction "1_1") (pintype "passive"))
    )
    (net (code "52") (name "Net-(D32-PadC)") (class "Default")
      (node (ref "D32") (pin "C") (pinfunction "C_C") (pintype "passive"))
      (node (ref "SW61") (pin "1") (pinfunction "1_1") (pintype "passive"))
    )
    (net (code "53") (name "Net-(D33-PadC)") (class "Default")
      (node (ref "D33") (pin "C") (pinfunction "C_C") (pintype "passive"))
      (node (ref "SW89") (pin "1") (pinfunction "1_1") (pintype "passive"))
    )
    (net (code "54") (name "Net-(D34-PadC)") (class "Default")
      (node (ref "D34") (pin "C") (pinfunction "C_C") (pintype "passive"))
      (node (ref "SW68") (pin "1") (pinfunction "1_1") (pintype "passive"))
    )
    (net (code "55") (name "Net-(D35-PadC)") (class "Default")
      (node (ref "D35") (pin "C") (pinfunction "C_C") (pintype "passive"))
      (node (ref "SW85") (pin "1") (pinfunction "1_1") (pintype "passive"))
    )
    (net (code "56") (name "Net-(D36-PadC)") (class "Default")
      (node (ref "D36") (pin "C") (pinfunction "C_C") (pintype "passive"))
      (node (ref "SW72") (pin "1") (pinfunction "1_1") (pintype "passive"))
    )
    (net (code "57") (name "Net-(D37-PadC)") (class "Default")
      (node (ref "D37") (pin "C") (pinfunction "C_C") (pintype "passive"))
      (node (ref "SW74") (pin "1") (pinfunction "1_1") (pintype "passive"))
    )
    (net (code "58") (name "Net-(D38-PadC)") (class "Default")
      (node (ref "D38") (pin "C") (pinfunction "C_C") (pintype "passive"))
      (node (ref "SW80") (pin "1") (pinfunction "1_1") (pintype "passive"))
    )
    (net (code "59") (name "Net-(D39-PadC)") (class "Default")
      (node (ref "D39") (pin "C") (pinfunction "C_C") (pintype "passive"))
      (node (ref "SW73") (pin "1") (pinfunction "1_1") (pintype "passive"))
    )
    (net (code "60") (name "Net-(D40-PadC)") (class "Default")
      (node (ref "D40") (pin "C") (pinfunction "C_C") (pintype "passive"))
      (node (ref "SW84") (pin "1") (pinfunction "1_1") (pintype "passive"))
    )
    (net (code "61") (name "Net-(D41-PadC)") (class "Default")
      (node (ref "D41") (pin "C") (pinfunction "C_C") (pintype "passive"))
      (node (ref "SW77") (pin "1") (pinfunction "1_1") (pintype "passive"))
    )
    (net (code "62") (name "Net-(D42-PadC)") (class "Default")
      (node (ref "D42") (pin "C") (pinfunction "C_C") (pintype "passive"))
      (node (ref "SW86") (pin "1") (pinfunction "1_1") (pintype "passive"))
    )
    (net (code "63") (name "Net-(D43-PadC)") (class "Default")
      (node (ref "D43") (pin "C") (pinfunction "C_C") (pintype "passive"))
      (node (ref "SW75") (pin "1") (pinfunction "1_1") (pintype "passive"))
    )
    (net (code "64") (name "Net-(D44-PadC)") (class "Default")
      (node (ref "D44") (pin "C") (pinfunction "C_C") (pintype "passive"))
      (node (ref "SW76") (pin "1") (pinfunction "1_1") (pintype "passive"))
    )
    (net (code "65") (name "Net-(D45-PadC)") (class "Default")
      (node (ref "D45") (pin "C") (pinfunction "C_C") (pintype "passive"))
      (node (ref "SW87") (pin "1") (pinfunction "1_1") (pintype "passive"))
    )
    (net (code "66") (name "Net-(D46-Pad+)") (class "Default")
      (node (ref "D46") (pin "+") (pinfunction "+_+") (pintype "passive"))
      (node (ref "R2") (pin "2") (pinfunction "2_2") (pintype "bidirectional"))
    )
    (net (code "67") (name "Net-(D47-Pad+)") (class "Default")
      (node (ref "D47") (pin "+") (pinfunction "+_+") (pintype "passive"))
      (node (ref "R1") (pin "2") (pinfunction "2_2") (pintype "bidirectional"))
    )
    (net (code "68") (name "Net-(IC1A-O)") (class "Default")
      (node (ref "IC1") (pin "2") (pinfunction "O_2") (pintype "output"))
      (node (ref "IC1") (pin "3") (pinfunction "I_3") (pintype "input"))
      (node (ref "IC1") (pin "5") (pinfunction "I_5") (pintype "input"))
    )
    (net (code "69") (name "Net-(IC1B-O)") (class "Default")
      (node (ref "IC1") (pin "4") (pinfunction "O_4") (pintype "output"))
      (node (ref "R3") (pin "2") (pinfunction "2_2") (pintype "bidirectional"))
    )
    (net (code "70") (name "Net-(IC1C-O)") (class "Default")
      (node (ref "IC1") (pin "6") (pinfunction "O_6") (pintype "output"))
      (node (ref "R1") (pin "1") (pinfunction "1_1") (pintype "bidirectional"))
    )
    (net (code "71") (name "Net-(IC1D-I)") (class "Default")
      (node (ref "IC1") (pin "10") (pinfunction "O_10") (pintype "output"))
      (node (ref "IC1") (pin "13") (pinfunction "I_13") (pintype "input"))
      (node (ref "IC1") (pin "9") (pinfunction "I_9") (pintype "input"))
    )
    (net (code "72") (name "Net-(IC1D-O)") (class "Default")
      (node (ref "IC1") (pin "8") (pinfunction "O_8") (pintype "output"))
      (node (ref "R2") (pin "1") (pinfunction "1_1") (pintype "bidirectional"))
    )
    (net (code "73") (name "Net-(IC1F-O)") (class "Default")
      (node (ref "IC1") (pin "12") (pinfunction "O_12") (pintype "output"))
      (node (ref "R4") (pin "2") (pinfunction "2_2") (pintype "bidirectional"))
    )
    (net (code "74") (name "Net-(LED1-DO)") (class "Default")
      (node (ref "LED1") (pin "DOUT") (pinfunction "DO_DOUT") (pintype "bidirectional"))
      (node (ref "LED2") (pin "DIN") (pinfunction "DI_DIN") (pintype "bidirectional"))
    )
    (net (code "75") (name "Net-(LED2-DO)") (class "Default")
      (node (ref "LED2") (pin "DOUT") (pinfunction "DO_DOUT") (pintype "bidirectional"))
      (node (ref "LED3") (pin "DIN") (pinfunction "DI_DIN") (pintype "bidirectional"))
    )
    (net (code "76") (name "Net-(LED3-DO)") (class "Default")
      (node (ref "LED3") (pin "DOUT") (pinfunction "DO_DOUT") (pintype "bidirectional"))
      (node (ref "LED4") (pin "DIN") (pinfunction "DI_DIN") (pintype "bidirectional"))
    )
    (net (code "77") (name "Net-(LED4-DO)") (class "Default")
      (node (ref "LED4") (pin "DOUT") (pinfunction "DO_DOUT") (pintype "bidirectional"))
      (node (ref "LED5") (pin "DIN") (pinfunction "DI_DIN") (pintype "bidirectional"))
    )
    (net (code "78") (name "Net-(LED5-DO)") (class "Default")
      (node (ref "LED5") (pin "DOUT") (pinfunction "DO_DOUT") (pintype "bidirectional"))
      (node (ref "LED6") (pin "DIN") (pinfunction "DI_DIN") (pintype "bidirectional"))
    )
    (net (code "79") (name "Net-(LED6-DO)") (class "Default")
      (node (ref "LED6") (pin "DOUT") (pinfunction "DO_DOUT") (pintype "bidirectional"))
      (node (ref "LED7") (pin "DIN") (pinfunction "DI_DIN") (pintype "bidirectional"))
    )
    (net (code "80") (name "Net-(LED7-DO)") (class "Default")
      (node (ref "LED7") (pin "DOUT") (pinfunction "DO_DOUT") (pintype "bidirectional"))
      (node (ref "LED8") (pin "DIN") (pinfunction "DI_DIN") (pintype "bidirectional"))
    )
    (net (code "81") (name "Net-(LED8-DO)") (class "Default")
      (node (ref "LED8") (pin "DOUT") (pinfunction "DO_DOUT") (pintype "bidirectional"))
      (node (ref "LED9") (pin "DIN") (pinfunction "DI_DIN") (pintype "bidirectional"))
    )
    (net (code "82") (name "Net-(LED10-DI)") (class "Default")
      (node (ref "LED10") (pin "DIN") (pinfunction "DI_DIN") (pintype "bidirectional"))
      (node (ref "LED9") (pin "DOUT") (pinfunction "DO_DOUT") (pintype "bidirectional"))
    )
    (net (code "83") (name "Net-(LED10-DO)") (class "Default")
      (node (ref "LED10") (pin "DOUT") (pinfunction "DO_DOUT") (pintype "bidirectional"))
      (node (ref "LED11") (pin "DIN") (pinfunction "DI_DIN") (pintype "bidirectional"))
    )
    (net (code "84") (name "Net-(LED11-DO)") (class "Default")
      (node (ref "LED11") (pin "DOUT") (pinfunction "DO_DOUT") (pintype "bidirectional"))
      (node (ref "LED12") (pin "DIN") (pinfunction "DI_DIN") (pintype "bidirectional"))
    )
    (net (code "85") (name "Net-(R3-Pad1)") (class "Default")
      (node (ref "R3") (pin "1") (pinfunction "1_1") (pintype "bidirectional"))
      (node (ref "U$11") (pin "5") (pinfunction "5_5") (pintype "passive"))
    )
    (net (code "86") (name "Net-(R4-Pad1)") (class "Default")
      (node (ref "R4") (pin "1") (pinfunction "1_1") (pintype "bidirectional"))
      (node (ref "U$4") (pin "5") (pinfunction "5_5") (pintype "passive"))
    )
    (net (code "87") (name "Net-(R5-Pad2)") (class "Default")
      (node (ref "R5") (pin "2") (pinfunction "2_2") (pintype "bidirectional"))
      (node (ref "U$11") (pin "4") (pinfunction "4_4") (pintype "passive"))
    )
    (net (code "88") (name "Net-(R6-Pad2)") (class "Default")
      (node (ref "R6") (pin "2") (pinfunction "2_2") (pintype "bidirectional"))
      (node (ref "U$4") (pin "4") (pinfunction "4_4") (pintype "passive"))
    )
    (net (code "89") (name "unconnected-(LED12-DO-PadDOUT)") (class "Default")
      (node (ref "LED12") (pin "DOUT") (pinfunction "DO_DOUT") (pintype "bidirectional"))
    )
    (net (code "90") (name "unconnected-(U$1-RESET-Pad22)") (class "Default")
      (node (ref "U$1") (pin "22") (pinfunction "RESET_22") (pintype "bidirectional"))
    )
    (net (code "91") (name "unconnected-(U$1-VCC-Pad21)") (class "Default")
      (node (ref "U$1") (pin "21") (pinfunction "VCC_21") (pintype "bidirectional"))
    )
    (net (code "92") (name "unconnected-(U$4-Pad1)") (class "Default")
      (node (ref "U$4") (pin "1") (pinfunction "1_1") (pintype "passive"))
    )
    (net (code "93") (name "unconnected-(U$4-Pad2)") (class "Default")
      (node (ref "U$4") (pin "2") (pinfunction "2_2") (pintype "passive"))
    )
    (net (code "94") (name "unconnected-(U$4-Pad3)") (class "Default")
      (node (ref "U$4") (pin "3") (pinfunction "3_3") (pintype "passive"))
    )
    (net (code "95") (name "unconnected-(U$4D-MT-PadPE1)") (class "Default")
      (node (ref "U$4") (pin "PE1") (pinfunction "MT_PE1") (pintype "passive"))
    )
    (net (code "96") (name "unconnected-(U$4E-MT-PadPE2)") (class "Default")
      (node (ref "U$4") (pin "PE2") (pinfunction "MT_PE2") (pintype "passive"))
    )
    (net (code "97") (name "unconnected-(U$11-Pad1)") (class "Default")
      (node (ref "U$11") (pin "1") (pinfunction "1_1") (pintype "passive"))
    )
    (net (code "98") (name "unconnected-(U$11-Pad2)") (class "Default")
      (node (ref "U$11") (pin "2") (pinfunction "2_2") (pintype "passive"))
    )
    (net (code "99") (name "unconnected-(U$11-Pad3)") (class "Default")
      (node (ref "U$11") (pin "3") (pinfunction "3_3") (pintype "passive"))
    )
  )
)
